# tester.net
KiCad netlist of a schematic drawn in EAGLE
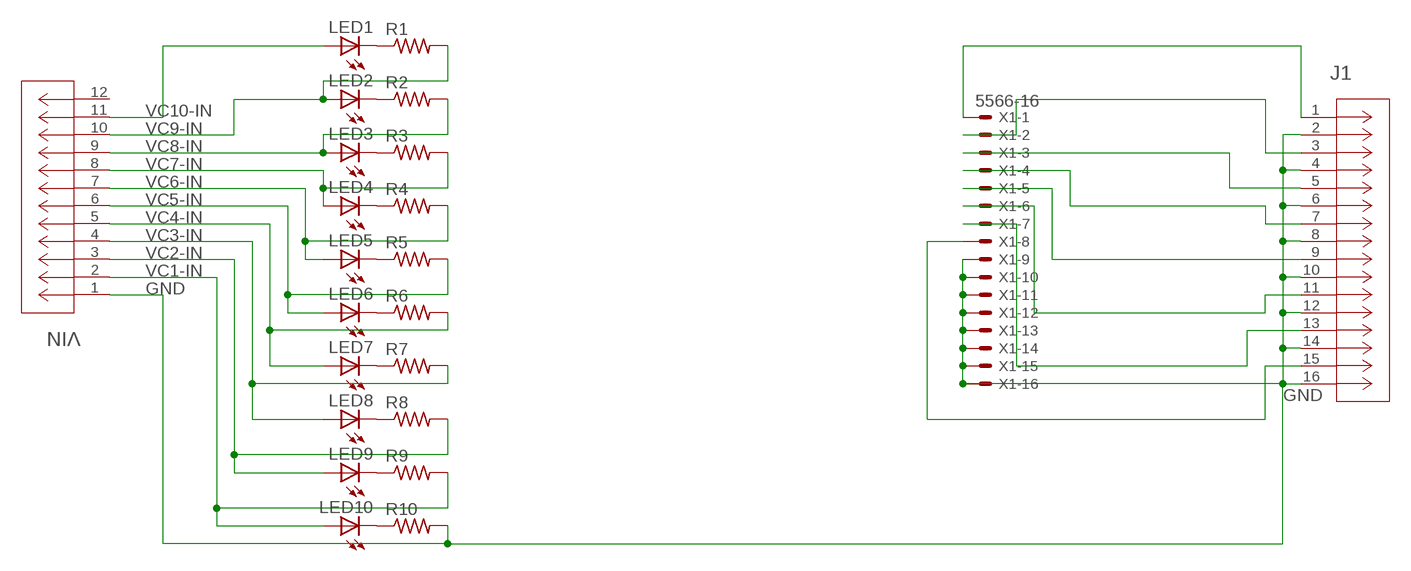
[diagram p0: schematic, sheet 1]

(export (version "E")
  (design (tool "Eeschema 10.0.6"))
  (components
    (comp (ref "J1")
      (value "DF11-16DP-2DSA(01)")
      (footprint "eagle-import:CONN_DF11-16DP-2DSA(01)_HIR")
      (fields (field (name "COPYRIGHT") "Copyright (C) 2023 Ultra Librarian. All rights reserved."))
      (libsource (lib "eagle-import") (part "DF11-16DP-2DSA(01)"))
    )
    (comp (ref "LED1")
      (value "LEDCHIPLED_0603")
      (footprint "eagle-import:CHIPLED_0603")
      (libsource (lib "eagle-import") (part "LEDCHIPLED_0603"))
    )
    (comp (ref "LED2")
      (value "LEDCHIPLED_0603")
      (footprint "eagle-import:CHIPLED_0603")
      (libsource (lib "eagle-import") (part "LEDCHIPLED_0603"))
    )
    (comp (ref "LED3")
      (value "LEDCHIPLED_0603")
      (footprint "eagle-import:CHIPLED_0603")
      (libsource (lib "eagle-import") (part "LEDCHIPLED_0603"))
    )
    (comp (ref "LED4")
      (value "LEDCHIPLED_0603")
      (footprint "eagle-import:CHIPLED_0603")
      (libsource (lib "eagle-import") (part "LEDCHIPLED_0603"))
    )
    (comp (ref "LED5")
      (value "LEDCHIPLED_0603")
      (footprint "eagle-import:CHIPLED_0603")
      (libsource (lib "eagle-import") (part "LEDCHIPLED_0603"))
    )
    (comp (ref "LED6")
      (value "LEDCHIPLED_0603")
      (footprint "eagle-import:CHIPLED_0603")
      (libsource (lib "eagle-import") (part "LEDCHIPLED_0603"))
    )
    (comp (ref "LED7")
      (value "LEDCHIPLED_0603")
      (footprint "eagle-import:CHIPLED_0603")
      (libsource (lib "eagle-import") (part "LEDCHIPLED_0603"))
    )
    (comp (ref "LED8")
      (value "LEDCHIPLED_0603")
      (footprint "eagle-import:CHIPLED_0603")
      (libsource (lib "eagle-import") (part "LEDCHIPLED_0603"))
    )
    (comp (ref "LED9")
      (value "LEDCHIPLED_0603")
      (footprint "eagle-import:CHIPLED_0603")
      (libsource (lib "eagle-import") (part "LEDCHIPLED_0603"))
    )
    (comp (ref "LED10")
      (value "LEDCHIPLED_0603")
      (footprint "eagle-import:CHIPLED_0603")
      (libsource (lib "eagle-import") (part "LEDCHIPLED_0603"))
    )
    (comp (ref "R1")
      (value "R-US_R0805")
      (footprint "eagle-import:R0805")
      (libsource (lib "eagle-import") (part "R-US_R0805"))
    )
    (comp (ref "R2")
      (value "R-US_R0805")
      (footprint "eagle-import:R0805")
      (libsource (lib "eagle-import") (part "R-US_R0805"))
    )
    (comp (ref "R3")
      (value "R-US_R0805")
      (footprint "eagle-import:R0805")
      (libsource (lib "eagle-import") (part "R-US_R0805"))
    )
    (comp (ref "R4")
      (value "R-US_R0805")
      (footprint "eagle-import:R0805")
      (libsource (lib "eagle-import") (part "R-US_R0805"))
    )
    (comp (ref "R5")
      (value "R-US_R0805")
      (footprint "eagle-import:R0805")
      (libsource (lib "eagle-import") (part "R-US_R0805"))
    )
    (comp (ref "R6")
      (value "R-US_R0805")
      (footprint "eagle-import:R0805")
      (libsource (lib "eagle-import") (part "R-US_R0805"))
    )
    (comp (ref "R7")
      (value "R-US_R0805")
      (footprint "eagle-import:R0805")
      (libsource (lib "eagle-import") (part "R-US_R0805"))
    )
    (comp (ref "R8")
      (value "R-US_R0805")
      (footprint "eagle-import:R0805")
      (libsource (lib "eagle-import") (part "R-US_R0805"))
    )
    (comp (ref "R9")
      (value "R-US_R0805")
      (footprint "eagle-import:R0805")
      (libsource (lib "eagle-import") (part "R-US_R0805"))
    )
    (comp (ref "R10")
      (value "R-US_R0805")
      (footprint "eagle-import:R0805")
      (libsource (lib "eagle-import") (part "R-US_R0805"))
    )
    (comp (ref "VIN")
      (value "DF11-12DP-2DSA(01)")
      (footprint "eagle-import:CON12_2X6_UF_DF11_HIR")
      (fields (field (name "COPYRIGHT") "Copyright (C) 2023 Ultra Librarian. All rights reserved."))
      (libsource (lib "eagle-import") (part "DF11-12DP-2DSA(01)"))
    )
    (comp (ref "X1")
      (value "5566-16")
      (footprint "eagle-import:5566-16")
      (fields (field (name "MF") "MOLEX"))
      (libsource (lib "eagle-import") (part "5566-16"))
    )
  )
  (nets
    (net (code "1") (name "/GND") (class "Default")
      (node (ref "J1") (pin "10") (pinfunction "10_10") (pintype "passive"))
      (node (ref "J1") (pin "12") (pinfunction "12_12") (pintype "passive"))
      (node (ref "J1") (pin "14") (pinfunction "14_14") (pintype "passive"))
      (node (ref "J1") (pin "16") (pinfunction "16_16") (pintype "passive"))
      (node (ref "J1") (pin "2") (pinfunction "2_2") (pintype "passive"))
      (node (ref "J1") (pin "4") (pinfunction "4_4") (pintype "passive"))
      (node (ref "J1") (pin "6") (pinfunction "6_6") (pintype "passive"))
      (node (ref "J1") (pin "8") (pinfunction "8_8") (pintype "passive"))
      (node (ref "R10") (pin "2") (pinfunction "2_2") (pintype "passive"))
      (node (ref "VIN") (pin "1") (pinfunction "1_1") (pintype "passive"))
      (node (ref "X1") (pin "10") (pinfunction "S_10") (pintype "passive"))
      (node (ref "X1") (pin "11") (pinfunction "S_11") (pintype "passive"))
      (node (ref "X1") (pin "12") (pinfunction "S_12") (pintype "passive"))
      (node (ref "X1") (pin "13") (pinfunction "S_13") (pintype "passive"))
      (node (ref "X1") (pin "14") (pinfunction "S_14") (pintype "passive"))
      (node (ref "X1") (pin "15") (pinfunction "S_15") (pintype "passive"))
      (node (ref "X1") (pin "16") (pinfunction "S_16") (pintype "passive"))
      (node (ref "X1") (pin "9") (pinfunction "S_9") (pintype "passive"))
    )
    (net (code "2") (name "/VC1-IN") (class "Default")
      (node (ref "LED10") (pin "A") (pinfunction "A_A") (pintype "passive"))
      (node (ref "R9") (pin "2") (pinfunction "2_2") (pintype "passive"))
      (node (ref "VIN") (pin "2") (pinfunction "2_2") (pintype "passive"))
    )
    (net (code "3") (name "/VC2-IN") (class "Default")
      (node (ref "LED9") (pin "A") (pinfunction "A_A") (pintype "passive"))
      (node (ref "R8") (pin "2") (pinfunction "2_2") (pintype "passive"))
      (node (ref "VIN") (pin "3") (pinfunction "3_3") (pintype "passive"))
    )
    (net (code "4") (name "/VC3-IN") (class "Default")
      (node (ref "LED8") (pin "A") (pinfunction "A_A") (pintype "passive"))
      (node (ref "R7") (pin "2") (pinfunction "2_2") (pintype "passive"))
      (node (ref "VIN") (pin "4") (pinfunction "4_4") (pintype "passive"))
    )
    (net (code "5") (name "/VC4-IN") (class "Default")
      (node (ref "LED7") (pin "A") (pinfunction "A_A") (pintype "passive"))
      (node (ref "R6") (pin "2") (pinfunction "2_2") (pintype "passive"))
      (node (ref "VIN") (pin "5") (pinfunction "5_5") (pintype "passive"))
    )
    (net (code "6") (name "/VC5-IN") (class "Default")
      (node (ref "LED6") (pin "A") (pinfunction "A_A") (pintype "passive"))
      (node (ref "R5") (pin "2") (pinfunction "2_2") (pintype "passive"))
      (node (ref "VIN") (pin "6") (pinfunction "6_6") (pintype "passive"))
    )
    (net (code "7") (name "/VC6-IN") (class "Default")
      (node (ref "LED5") (pin "A") (pinfunction "A_A") (pintype "passive"))
      (node (ref "R4") (pin "2") (pinfunction "2_2") (pintype "passive"))
      (node (ref "VIN") (pin "7") (pinfunction "7_7") (pintype "passive"))
    )
    (net (code "8") (name "/VC7-IN") (class "Default")
      (node (ref "LED4") (pin "A") (pinfunction "A_A") (pintype "passive"))
      (node (ref "R3") (pin "2") (pinfunction "2_2") (pintype "passive"))
      (node (ref "VIN") (pin "8") (pinfunction "8_8") (pintype "passive"))
    )
    (net (code "9") (name "/VC8-IN") (class "Default")
      (node (ref "LED3") (pin "A") (pinfunction "A_A") (pintype "passive"))
      (node (ref "R2") (pin "2") (pinfunction "2_2") (pintype "passive"))
      (node (ref "VIN") (pin "9") (pinfunction "9_9") (pintype "passive"))
    )
    (net (code "10") (name "/VC9-IN") (class "Default")
      (node (ref "LED2") (pin "A") (pinfunction "A_A") (pintype "passive"))
      (node (ref "R1") (pin "2") (pinfunction "2_2") (pintype "passive"))
      (node (ref "VIN") (pin "10") (pinfunction "10_10") (pintype "passive"))
    )
    (net (code "11") (name "/VC10-IN") (class "Default")
      (node (ref "LED1") (pin "A") (pinfunction "A_A") (pintype "passive"))
      (node (ref "VIN") (pin "11") (pinfunction "11_11") (pintype "passive"))
    )
    (net (code "12") (name "Net-(LED1-PadC)") (class "Default")
      (node (ref "LED1") (pin "C") (pinfunction "C_C") (pintype "passive"))
      (node (ref "R1") (pin "1") (pinfunction "1_1") (pintype "passive"))
    )
    (net (code "13") (name "Net-(LED2-PadC)") (class "Default")
      (node (ref "LED2") (pin "C") (pinfunction "C_C") (pintype "passive"))
      (node (ref "R2") (pin "1") (pinfunction "1_1") (pintype "passive"))
    )
    (net (code "14") (name "Net-(LED3-PadC)") (class "Default")
      (node (ref "LED3") (pin "C") (pinfunction "C_C") (pintype "passive"))
      (node (ref "R3") (pin "1") (pinfunction "1_1") (pintype "passive"))
    )
    (net (code "15") (name "Net-(LED4-PadC)") (class "Default")
      (node (ref "LED4") (pin "C") (pinfunction "C_C") (pintype "passive"))
      (node (ref "R4") (pin "1") (pinfunction "1_1") (pintype "passive"))
    )
    (net (code "16") (name "Net-(LED5-PadC)") (class "Default")
      (node (ref "LED5") (pin "C") (pinfunction "C_C") (pintype "passive"))
      (node (ref "R5") (pin "1") (pinfunction "1_1") (pintype "passive"))
    )
    (net (code "17") (name "Net-(LED6-PadC)") (class "Default")
      (node (ref "LED6") (pin "C") (pinfunction "C_C") (pintype "passive"))
      (node (ref "R6") (pin "1") (pinfunction "1_1") (pintype "passive"))
    )
    (net (code "18") (name "Net-(LED7-PadC)") (class "Default")
      (node (ref "LED7") (pin "C") (pinfunction "C_C") (pintype "passive"))
      (node (ref "R7") (pin "1") (pinfunction "1_1") (pintype "passive"))
    )
    (net (code "19") (name "Net-(LED8-PadC)") (class "Default")
      (node (ref "LED8") (pin "C") (pinfunction "C_C") (pintype "passive"))
      (node (ref "R8") (pin "1") (pinfunction "1_1") (pintype "passive"))
    )
    (net (code "20") (name "Net-(LED9-PadC)") (class "Default")
      (node (ref "LED9") (pin "C") (pinfunction "C_C") (pintype "passive"))
      (node (ref "R9") (pin "1") (pinfunction "1_1") (pintype "passive"))
    )
    (net (code "21") (name "Net-(LED10-PadC)") (class "Default")
      (node (ref "LED10") (pin "C") (pinfunction "C_C") (pintype "passive"))
      (node (ref "R10") (pin "1") (pinfunction "1_1") (pintype "passive"))
    )
    (net (code "22") (name "Net-(X1A-S)") (class "Default")
      (node (ref "J1") (pin "1") (pinfunction "1_1") (pintype "passive"))
      (node (ref "X1") (pin "1") (pinfunction "S_1") (pintype "passive"))
    )
    (net (code "23") (name "Net-(X1I-S)") (class "Default")
      (node (ref "J1") (pin "3") (pinfunction "3_3") (pintype "passive"))
      (node (ref "X1") (pin "2") (pinfunction "S_2") (pintype "passive"))
    )
    (net (code "24") (name "Net-(X1J-S)") (class "Default")
      (node (ref "J1") (pin "5") (pinfunction "5_5") (pintype "passive"))
      (node (ref "X1") (pin "3") (pinfunction "S_3") (pintype "passive"))
    )
    (net (code "25") (name "Net-(X1K-S)") (class "Default")
      (node (ref "J1") (pin "7") (pinfunction "7_7") (pintype "passive"))
      (node (ref "X1") (pin "4") (pinfunction "S_4") (pintype "passive"))
    )
    (net (code "26") (name "Net-(X1L-S)") (class "Default")
      (node (ref "J1") (pin "9") (pinfunction "9_9") (pintype "passive"))
      (node (ref "X1") (pin "5") (pinfunction "S_5") (pintype "passive"))
    )
    (net (code "27") (name "Net-(X1M-S)") (class "Default")
      (node (ref "J1") (pin "11") (pinfunction "11_11") (pintype "passive"))
      (node (ref "X1") (pin "6") (pinfunction "S_6") (pintype "passive"))
    )
    (net (code "28") (name "Net-(X1N-S)") (class "Default")
      (node (ref "J1") (pin "13") (pinfunction "13_13") (pintype "passive"))
      (node (ref "X1") (pin "7") (pinfunction "S_7") (pintype "passive"))
    )
    (net (code "29") (name "Net-(X1O-S)") (class "Default")
      (node (ref "J1") (pin "15") (pinfunction "15_15") (pintype "passive"))
      (node (ref "X1") (pin "8") (pinfunction "S_8") (pintype "passive"))
    )
    (net (code "30") (name "unconnected-(VIN-Pad12)") (class "Default")
      (node (ref "VIN") (pin "12") (pinfunction "12_12") (pintype "passive"))
    )
  )
)
